# tek611.net
KiCad netlist of a schematic drawn in EAGLE
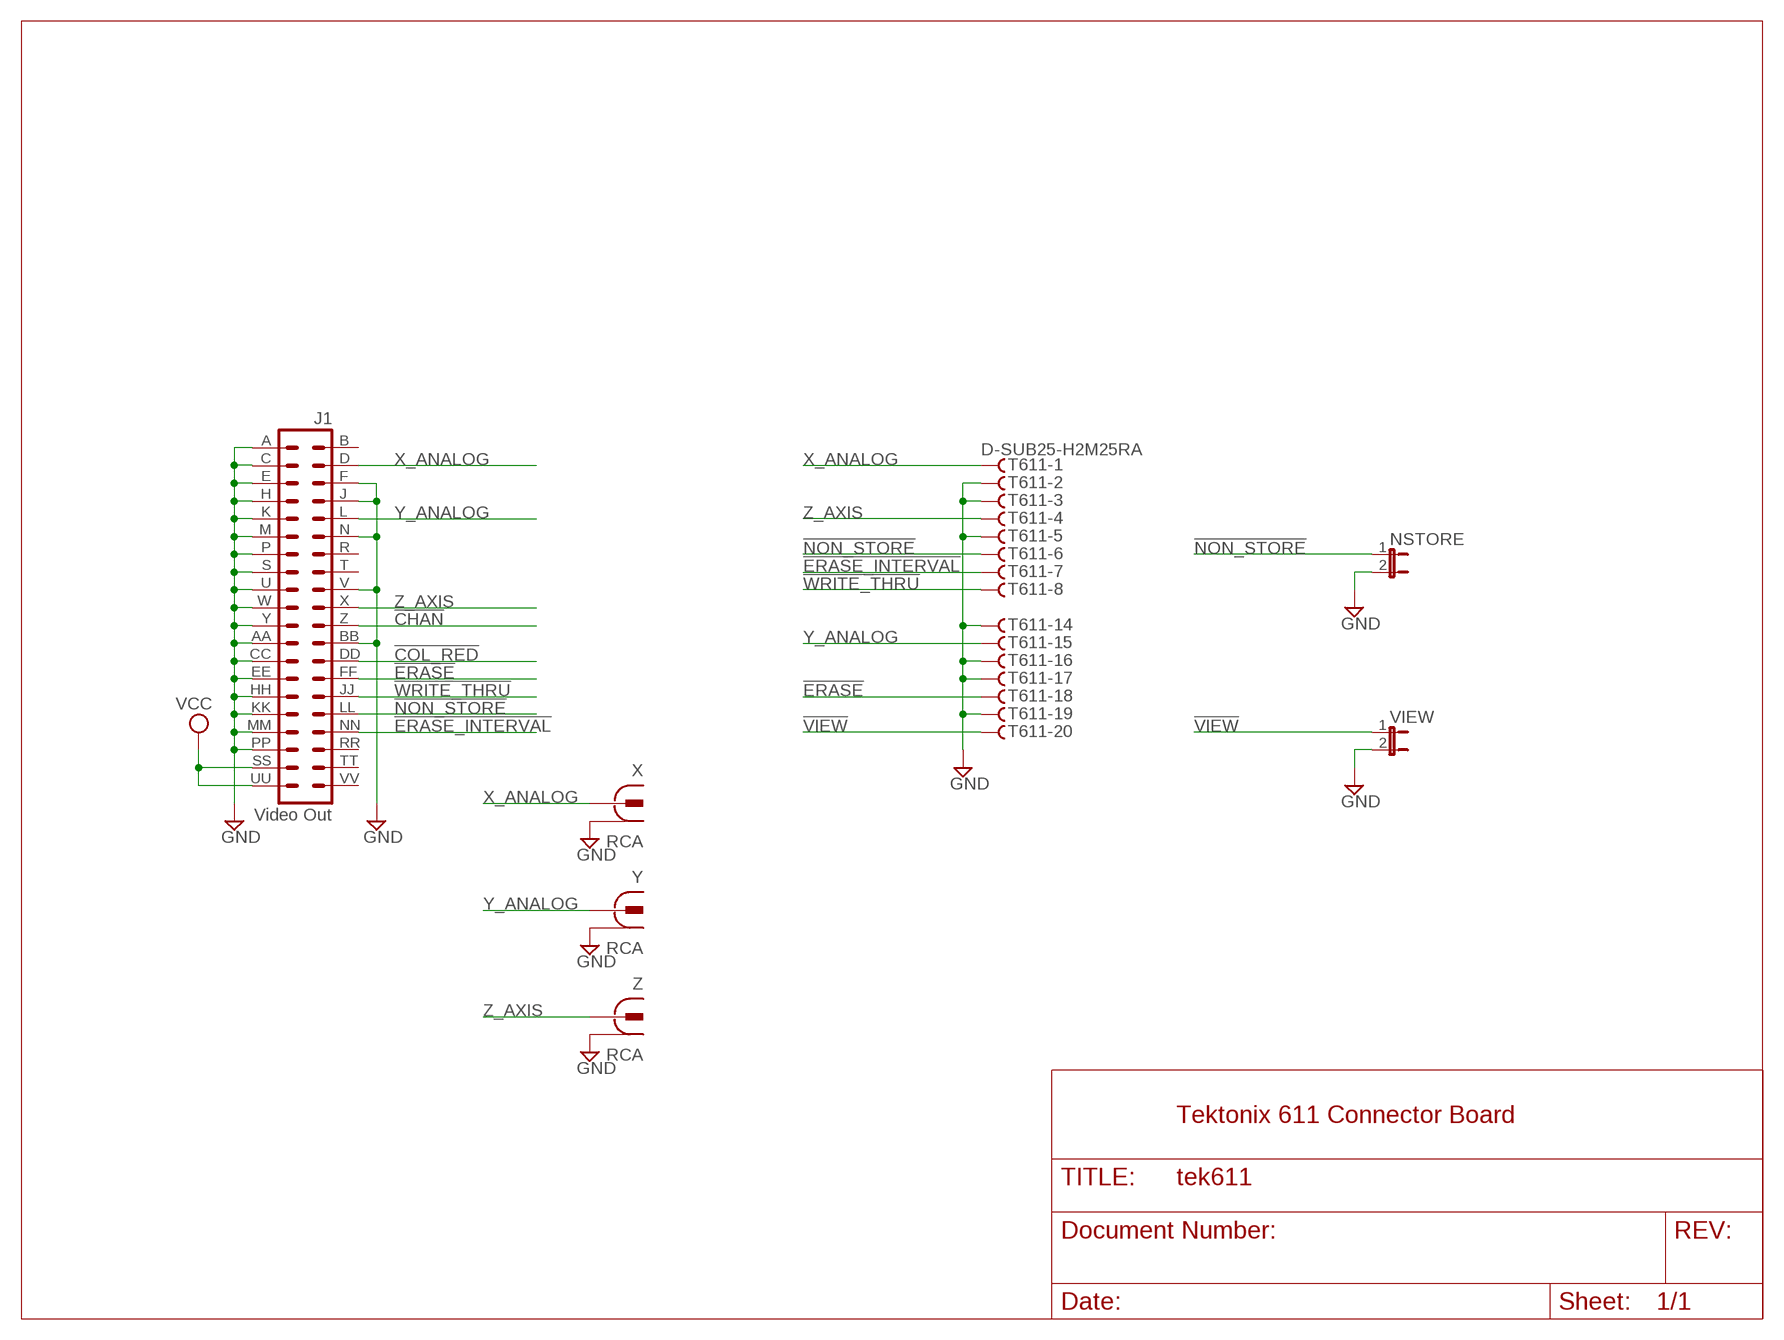
[diagram p0: schematic, sheet 1]

(export (version "E")
  (design (tool "Eeschema 10.0.6"))
  (components
    (comp (ref "J1")
      (value "Video Out")
      (footprint "eagle-import:DEC40PINH")
      (libsource (lib "eagle-import") (part "DEC40PINH"))
    )
    (comp (ref "NSTORE")
      (value "JP1E")
      (footprint "eagle-import:JP1")
      (libsource (lib "eagle-import") (part "JP1E"))
    )
    (comp (ref "T611")
      (value "D-SUB25-H2M25RA")
      (footprint "eagle-import:H2M25RA")
      (libsource (lib "eagle-import") (part "D-SUB25-H2M25RA"))
    )
    (comp (ref "VIEW")
      (value "JP1E")
      (footprint "eagle-import:JP1")
      (libsource (lib "eagle-import") (part "JP1E"))
    )
    (comp (ref "X")
      (value "RCA")
      (footprint "eagle-import:RCA")
      (libsource (lib "eagle-import") (part "RCA"))
    )
    (comp (ref "Y")
      (value "RCA")
      (footprint "eagle-import:RCA")
      (libsource (lib "eagle-import") (part "RCA"))
    )
    (comp (ref "Z")
      (value "RCA")
      (footprint "eagle-import:RCA")
      (libsource (lib "eagle-import") (part "RCA"))
    )
  )
  (nets
    (net (code "1") (name "/X_ANALOG") (class "Default")
      (node (ref "J1") (pin "D") (pinfunction "4_D") (pintype "bidirectional"))
      (node (ref "T611") (pin "1") (pinfunction "F_1") (pintype "passive"))
      (node (ref "X") (pin "2") (pinfunction "2_2") (pintype "passive"))
    )
    (net (code "2") (name "/Y_ANALOG") (class "Default")
      (node (ref "J1") (pin "L") (pinfunction "10_L") (pintype "bidirectional"))
      (node (ref "T611") (pin "15") (pinfunction "F_15") (pintype "passive"))
      (node (ref "Y") (pin "2") (pinfunction "2_2") (pintype "passive"))
    )
    (net (code "3") (name "/Z_AXIS") (class "Default")
      (node (ref "J1") (pin "X") (pinfunction "20_X") (pintype "bidirectional"))
      (node (ref "T611") (pin "4") (pinfunction "F_4") (pintype "passive"))
      (node (ref "Z") (pin "2") (pinfunction "2_2") (pintype "passive"))
    )
    (net (code "4") (name "/~{CHAN}") (class "Default")
      (node (ref "J1") (pin "Z") (pinfunction "22_Z") (pintype "bidirectional"))
    )
    (net (code "5") (name "/~{COL_RED}") (class "Default")
      (node (ref "J1") (pin "DD") (pinfunction "26_DD") (pintype "bidirectional"))
    )
    (net (code "6") (name "/~{ERASE_INTERVAL}") (class "Default")
      (node (ref "J1") (pin "NN") (pinfunction "34_NN") (pintype "bidirectional"))
      (node (ref "T611") (pin "7") (pinfunction "F_7") (pintype "passive"))
    )
    (net (code "7") (name "/~{ERASE}") (class "Default")
      (node (ref "J1") (pin "FF") (pinfunction "28_FF") (pintype "bidirectional"))
      (node (ref "T611") (pin "18") (pinfunction "F_18") (pintype "passive"))
    )
    (net (code "8") (name "/~{NON_STORE}") (class "Default")
      (node (ref "J1") (pin "LL") (pinfunction "32_LL") (pintype "bidirectional"))
      (node (ref "NSTORE") (pin "1") (pinfunction "1_1") (pintype "passive"))
      (node (ref "T611") (pin "6") (pinfunction "F_6") (pintype "passive"))
    )
    (net (code "9") (name "/~{VIEW}") (class "Default")
      (node (ref "T611") (pin "20") (pinfunction "F_20") (pintype "passive"))
      (node (ref "VIEW") (pin "1") (pinfunction "1_1") (pintype "passive"))
    )
    (net (code "10") (name "/~{WRITE_THRU}") (class "Default")
      (node (ref "J1") (pin "JJ") (pinfunction "30_JJ") (pintype "bidirectional"))
      (node (ref "T611") (pin "8") (pinfunction "F_8") (pintype "passive"))
    )
    (net (code "11") (name "GND") (class "Default")
      (node (ref "J1") (pin "A") (pinfunction "1_A") (pintype "bidirectional"))
      (node (ref "J1") (pin "AA") (pinfunction "23_AA") (pintype "bidirectional"))
      (node (ref "J1") (pin "BB") (pinfunction "24_BB") (pintype "bidirectional"))
      (node (ref "J1") (pin "C") (pinfunction "3_C") (pintype "bidirectional"))
      (node (ref "J1") (pin "CC") (pinfunction "25_CC") (pintype "bidirectional"))
      (node (ref "J1") (pin "E") (pinfunction "5_E") (pintype "bidirectional"))
      (node (ref "J1") (pin "EE") (pinfunction "27_EE") (pintype "bidirectional"))
      (node (ref "J1") (pin "F") (pinfunction "6_F") (pintype "bidirectional"))
      (node (ref "J1") (pin "H") (pinfunction "7_H") (pintype "bidirectional"))
      (node (ref "J1") (pin "HH") (pinfunction "29_HH") (pintype "bidirectional"))
      (node (ref "J1") (pin "J") (pinfunction "8_J") (pintype "bidirectional"))
      (node (ref "J1") (pin "K") (pinfunction "9_K") (pintype "bidirectional"))
      (node (ref "J1") (pin "KK") (pinfunction "31_KK") (pintype "bidirectional"))
      (node (ref "J1") (pin "M") (pinfunction "11_M") (pintype "bidirectional"))
      (node (ref "J1") (pin "MM") (pinfunction "33_MM") (pintype "bidirectional"))
      (node (ref "J1") (pin "N") (pinfunction "12_N") (pintype "bidirectional"))
      (node (ref "J1") (pin "P") (pinfunction "13_P") (pintype "bidirectional"))
      (node (ref "J1") (pin "PP") (pinfunction "35_PP") (pintype "bidirectional"))
      (node (ref "J1") (pin "S") (pinfunction "15_S") (pintype "bidirectional"))
      (node (ref "J1") (pin "U") (pinfunction "17_U") (pintype "bidirectional"))
      (node (ref "J1") (pin "V") (pinfunction "18_V") (pintype "bidirectional"))
      (node (ref "J1") (pin "W") (pinfunction "19_W") (pintype "bidirectional"))
      (node (ref "J1") (pin "Y") (pinfunction "21_Y") (pintype "bidirectional"))
      (node (ref "NSTORE") (pin "2") (pinfunction "2_2") (pintype "passive"))
      (node (ref "T611") (pin "14") (pinfunction "F_14") (pintype "passive"))
      (node (ref "T611") (pin "16") (pinfunction "F_16") (pintype "passive"))
      (node (ref "T611") (pin "17") (pinfunction "F_17") (pintype "passive"))
      (node (ref "T611") (pin "19") (pinfunction "F_19") (pintype "passive"))
      (node (ref "T611") (pin "2") (pinfunction "F_2") (pintype "passive"))
      (node (ref "T611") (pin "3") (pinfunction "F_3") (pintype "passive"))
      (node (ref "T611") (pin "5") (pinfunction "F_5") (pintype "passive"))
      (node (ref "VIEW") (pin "2") (pinfunction "2_2") (pintype "passive"))
      (node (ref "X") (pin "1") (pinfunction "1_1") (pintype "passive"))
      (node (ref "X") (pin "1@1") (pinfunction "1_1@1") (pintype "passive"))
      (node (ref "X") (pin "1@2") (pinfunction "1_1@2") (pintype "passive"))
      (node (ref "Y") (pin "1") (pinfunction "1_1") (pintype "passive"))
      (node (ref "Y") (pin "1@1") (pinfunction "1_1@1") (pintype "passive"))
      (node (ref "Y") (pin "1@2") (pinfunction "1_1@2") (pintype "passive"))
      (node (ref "Z") (pin "1") (pinfunction "1_1") (pintype "passive"))
      (node (ref "Z") (pin "1@1") (pinfunction "1_1@1") (pintype "passive"))
      (node (ref "Z") (pin "1@2") (pinfunction "1_1@2") (pintype "passive"))
    )
    (net (code "12") (name "VCC") (class "Default")
      (node (ref "J1") (pin "SS") (pinfunction "37_SS") (pintype "bidirectional"))
      (node (ref "J1") (pin "UU") (pinfunction "39_UU") (pintype "bidirectional"))
    )
    (net (code "13") (name "unconnected-(J1-2-PadB)") (class "Default")
      (node (ref "J1") (pin "B") (pinfunction "2_B") (pintype "bidirectional"))
    )
    (net (code "14") (name "unconnected-(J1-14-PadR)") (class "Default")
      (node (ref "J1") (pin "R") (pinfunction "14_R") (pintype "bidirectional"))
    )
    (net (code "15") (name "unconnected-(J1-16-PadT)") (class "Default")
      (node (ref "J1") (pin "T") (pinfunction "16_T") (pintype "bidirectional"))
    )
    (net (code "16") (name "unconnected-(J1-36-PadRR)") (class "Default")
      (node (ref "J1") (pin "RR") (pinfunction "36_RR") (pintype "bidirectional"))
    )
    (net (code "17") (name "unconnected-(J1-38-PadTT)") (class "Default")
      (node (ref "J1") (pin "TT") (pinfunction "38_TT") (pintype "bidirectional"))
    )
    (net (code "18") (name "unconnected-(J1-40-PadVV)") (class "Default")
      (node (ref "J1") (pin "VV") (pinfunction "40_VV") (pintype "bidirectional"))
    )
  )
)
